# Inverted_HS_switch_HI_PWR.net
KiCad netlist of a schematic drawn in Altium Designer
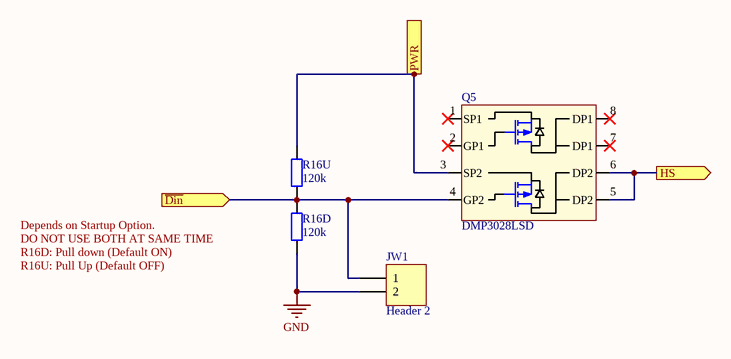
[diagram p0: Inverted_HS_switch_HI_PWR.SchDoc]

(export (version "E")
  (design (tool "Eeschema 10.0.6"))
  (components
    (comp (ref "JW1")
      (value "Header 2")
      (footprint "HDR1X2")
      (description "Header, 2-Pin, Optional short to GND for PFET")
      (fields (field (name "PUBLISHER") "Altium Limited"))
      (libsource (lib "Miscellaneous Connectors") (part "Header 2"))
    )
    (comp (ref "Q5")
      (value "DMP3028LSD")
      (footprint "SOIC-8_SOIC127P600X175-8N")
      (description "MOSFET 2P-CH 30V 6A SO-8, VgMax=20V, Max Drain Resistance (38 mΩ)")
      (fields
        (field (name "MANUFACTURER") "Diodes")
        (field (name "MANUFACTURER PART NUMBER") "DMP3028LSD-13")
      )
      (libsource (lib "Datalogger") (part "DMP3028LSD"))
    )
    (comp (ref "R16D")
      (value "120k")
      (footprint "RES-1206_M")
      (description "Resistor")
      (fields (field (name "PUBLISHER") "Altium Limited"))
      (libsource (lib "Datalogger") (part "Res2"))
    )
    (comp (ref "R16U")
      (value "120k")
      (footprint "RES-1206_M")
      (description "Resistor")
      (fields (field (name "PUBLISHER") "Altium Limited"))
      (libsource (lib "Datalogger") (part "Res2"))
    )
  )
  (nets
    (net (code "1") (name "/HS") (class "Default")
      (node (ref "Q5") (pin "5") (pinfunction "DP2_5") (pintype "passive"))
      (node (ref "Q5") (pin "6") (pinfunction "DP2_6") (pintype "passive"))
    )
    (net (code "2") (name "/PWR") (class "Default")
      (node (ref "Q5") (pin "3") (pinfunction "SP2_3") (pintype "passive"))
      (node (ref "R16U") (pin "2") (pinfunction "2_2") (pintype "passive"))
    )
    (net (code "3") (name "/~{Din}") (class "Default")
      (node (ref "JW1") (pin "1") (pinfunction "1_1") (pintype "passive"))
      (node (ref "Q5") (pin "4") (pinfunction "GP2_4") (pintype "passive"))
      (node (ref "R16D") (pin "2") (pinfunction "2_2") (pintype "passive"))
      (node (ref "R16U") (pin "1") (pinfunction "1_1") (pintype "passive"))
    )
    (net (code "4") (name "GND") (class "Default")
      (node (ref "JW1") (pin "2") (pinfunction "2_2") (pintype "passive"))
      (node (ref "R16D") (pin "1") (pinfunction "1_1") (pintype "passive"))
    )
    (net (code "5") (name "unconnected-(Q5-DP1-Pad7)") (class "Default")
      (node (ref "Q5") (pin "7") (pinfunction "DP1_7") (pintype "passive+no_connect"))
    )
    (net (code "6") (name "unconnected-(Q5-DP1-Pad8)") (class "Default")
      (node (ref "Q5") (pin "8") (pinfunction "DP1_8") (pintype "passive+no_connect"))
    )
    (net (code "7") (name "unconnected-(Q5-GP1-Pad2)") (class "Default")
      (node (ref "Q5") (pin "2") (pinfunction "GP1_2") (pintype "passive+no_connect"))
    )
    (net (code "8") (name "unconnected-(Q5-SP1-Pad1)") (class "Default")
      (node (ref "Q5") (pin "1") (pinfunction "SP1_1") (pintype "passive+no_connect"))
    )
  )
)
